# MCU.net
KiCad netlist of a schematic drawn in Altium Designer
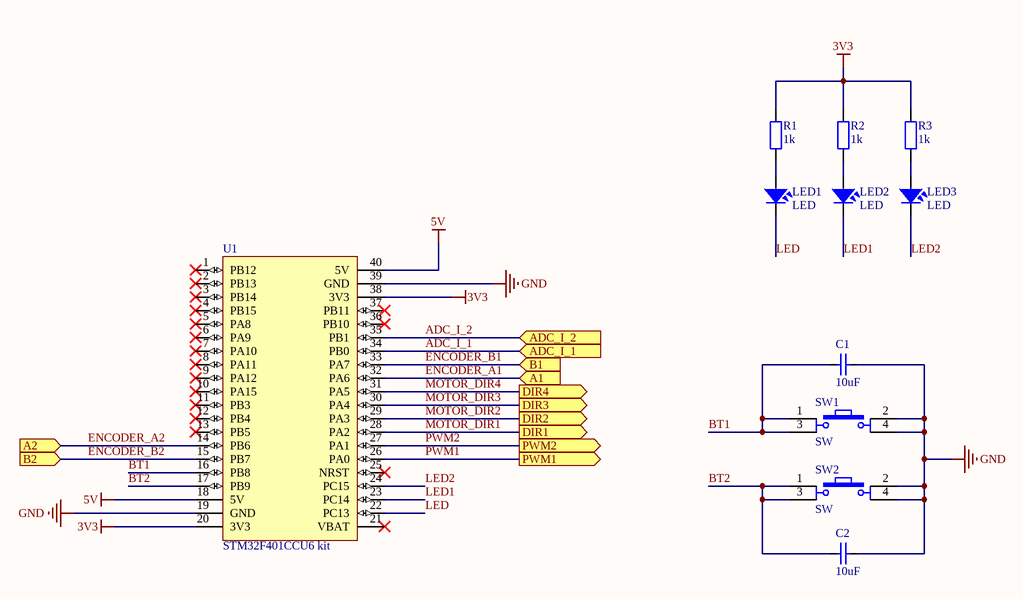
[diagram p0: MCU.SchDoc]

(export (version "E")
  (design (tool "Eeschema 10.0.6"))
  (components
    (comp (ref "C1")
      (value "10uF")
      (footprint "CAP_0805")
      (description "Capacitor")
      (fields (field (name "PUBLISHER") "Altium Limited"))
      (libsource (lib "My Library") (part "CapSMD"))
    )
    (comp (ref "C2")
      (value "10uF")
      (footprint "CAP_0805")
      (description "Capacitor")
      (fields (field (name "PUBLISHER") "Altium Limited"))
      (libsource (lib "My Library") (part "CapSMD"))
    )
    (comp (ref "LED1")
      (value "LED")
      (footprint "LED-0805-Red")
      (description "LED Single colour Green and Red")
      (libsource (lib "My Library") (part "LED"))
    )
    (comp (ref "LED2")
      (value "LED")
      (footprint "LED-0805-Orange")
      (description "LED Single colour Green and Red")
      (libsource (lib "My Library") (part "LED"))
    )
    (comp (ref "LED3")
      (value "LED")
      (footprint "LED-0805-Green")
      (description "LED Single colour Green and Red")
      (libsource (lib "My Library") (part "LED"))
    )
    (comp (ref "R1")
      (value "1k")
      (footprint "RES-SMD-0805")
      (description "Resistor SMD")
      (fields
        (field (name "MANUFACTURER") "Generic Components")
        (field (name "PUBLISHER") "Altium Hobart Technology Centre")
      )
      (libsource (lib "My Library") (part "Resistor - SMD"))
    )
    (comp (ref "R2")
      (value "1k")
      (footprint "RES-SMD-0805")
      (description "Resistor SMD")
      (fields
        (field (name "MANUFACTURER") "Generic Components")
        (field (name "PUBLISHER") "Altium Hobart Technology Centre")
      )
      (libsource (lib "My Library") (part "Resistor - SMD"))
    )
    (comp (ref "R3")
      (value "1k")
      (footprint "RES-SMD-0805")
      (description "Resistor SMD")
      (fields
        (field (name "MANUFACTURER") "Generic Components")
        (field (name "PUBLISHER") "Altium Hobart Technology Centre")
      )
      (libsource (lib "My Library") (part "Resistor - SMD"))
    )
    (comp (ref "SW1")
      (value "SW")
      (footprint "SW4")
      (description "Switch button 4 pin")
      (libsource (lib "My Library") (part "SW4"))
    )
    (comp (ref "SW2")
      (value "SW")
      (footprint "SW4")
      (description "Switch button 4 pin")
      (libsource (lib "My Library") (part "SW4"))
    )
    (comp (ref "U1")
      (value "STM32F401CCU6 kit")
      (footprint "STM32F401 KIT")
      (description "STM32F401CCU6 breakout board. STM32 ARM-based 32-bit MCU")
      (libsource (lib "My Library") (part "STM32F401CCU6"))
    )
  )
  (nets
    (net (code "1") (name "/ADC_I_1") (class "Default")
      (node (ref "U1") (pin "34") (pinfunction "PB0_34") (pintype "bidirectional"))
    )
    (net (code "2") (name "/ADC_I_2") (class "Default")
      (node (ref "U1") (pin "35") (pinfunction "PB1_35") (pintype "bidirectional"))
    )
    (net (code "3") (name "/BT1") (class "Default")
      (node (ref "C1") (pin "1") (pinfunction "1_1") (pintype "passive"))
      (node (ref "SW1") (pin "1") (pintype "passive"))
      (node (ref "SW1") (pin "3") (pintype "passive"))
      (node (ref "U1") (pin "16") (pinfunction "PB8_16") (pintype "bidirectional"))
    )
    (net (code "4") (name "/BT2") (class "Default")
      (node (ref "C2") (pin "1") (pinfunction "1_1") (pintype "passive"))
      (node (ref "SW2") (pin "1") (pintype "passive"))
      (node (ref "SW2") (pin "3") (pintype "passive"))
      (node (ref "U1") (pin "17") (pinfunction "PB9_17") (pintype "bidirectional"))
    )
    (net (code "5") (name "/ENCODER_A1") (class "Default")
      (node (ref "U1") (pin "32") (pinfunction "PA6_32") (pintype "bidirectional"))
    )
    (net (code "6") (name "/ENCODER_A2") (class "Default")
      (node (ref "U1") (pin "14") (pinfunction "PB6_14") (pintype "bidirectional"))
    )
    (net (code "7") (name "/ENCODER_B1") (class "Default")
      (node (ref "U1") (pin "33") (pinfunction "PA7_33") (pintype "bidirectional"))
    )
    (net (code "8") (name "/ENCODER_B2") (class "Default")
      (node (ref "U1") (pin "15") (pinfunction "PB7_15") (pintype "bidirectional"))
    )
    (net (code "9") (name "/LED") (class "Default")
      (node (ref "LED1") (pin "2") (pinfunction "2_2") (pintype "passive"))
      (node (ref "U1") (pin "22") (pinfunction "PC13_22") (pintype "bidirectional"))
    )
    (net (code "10") (name "/LED1") (class "Default")
      (node (ref "LED2") (pin "2") (pinfunction "2_2") (pintype "passive"))
      (node (ref "U1") (pin "23") (pinfunction "PC14_23") (pintype "bidirectional"))
    )
    (net (code "11") (name "/LED2") (class "Default")
      (node (ref "LED3") (pin "2") (pinfunction "2_2") (pintype "passive"))
      (node (ref "U1") (pin "24") (pinfunction "PC15_24") (pintype "bidirectional"))
    )
    (net (code "12") (name "/MOTOR_DIR1") (class "Default")
      (node (ref "U1") (pin "28") (pinfunction "PA2_28") (pintype "bidirectional"))
    )
    (net (code "13") (name "/MOTOR_DIR2") (class "Default")
      (node (ref "U1") (pin "29") (pinfunction "PA3_29") (pintype "bidirectional"))
    )
    (net (code "14") (name "/MOTOR_DIR3") (class "Default")
      (node (ref "U1") (pin "30") (pinfunction "PA4_30") (pintype "bidirectional"))
    )
    (net (code "15") (name "/MOTOR_DIR4") (class "Default")
      (node (ref "U1") (pin "31") (pinfunction "PA5_31") (pintype "bidirectional"))
    )
    (net (code "16") (name "/PWM1") (class "Default")
      (node (ref "U1") (pin "26") (pinfunction "PA0_26") (pintype "bidirectional"))
    )
    (net (code "17") (name "/PWM2") (class "Default")
      (node (ref "U1") (pin "27") (pinfunction "PA1_27") (pintype "bidirectional"))
    )
    (net (code "18") (name "3V3") (class "Default")
      (node (ref "R1") (pin "1") (pinfunction "1_1") (pintype "passive"))
      (node (ref "R2") (pin "1") (pinfunction "1_1") (pintype "passive"))
      (node (ref "R3") (pin "1") (pinfunction "1_1") (pintype "passive"))
      (node (ref "U1") (pin "20") (pinfunction "3V3_20") (pintype "power_in"))
      (node (ref "U1") (pin "38") (pinfunction "3V3_38") (pintype "power_in"))
    )
    (net (code "19") (name "5V") (class "Default")
      (node (ref "U1") (pin "18") (pinfunction "5V_18") (pintype "power_in"))
      (node (ref "U1") (pin "40") (pinfunction "5V_40") (pintype "power_in"))
    )
    (net (code "20") (name "GND") (class "Default")
      (node (ref "C1") (pin "2") (pinfunction "2_2") (pintype "passive"))
      (node (ref "C2") (pin "2") (pinfunction "2_2") (pintype "passive"))
      (node (ref "SW1") (pin "2") (pintype "passive"))
      (node (ref "SW1") (pin "4") (pintype "passive"))
      (node (ref "SW2") (pin "2") (pintype "passive"))
      (node (ref "SW2") (pin "4") (pintype "passive"))
      (node (ref "U1") (pin "19") (pinfunction "GND_19") (pintype "power_in"))
      (node (ref "U1") (pin "39") (pinfunction "GND_39") (pintype "power_in"))
    )
    (net (code "21") (name "Net-(LED1-Pad1)") (class "Default")
      (node (ref "LED1") (pin "1") (pinfunction "1_1") (pintype "passive"))
      (node (ref "R1") (pin "2") (pinfunction "2_2") (pintype "passive"))
    )
    (net (code "22") (name "Net-(LED2-Pad1)") (class "Default")
      (node (ref "LED2") (pin "1") (pinfunction "1_1") (pintype "passive"))
      (node (ref "R2") (pin "2") (pinfunction "2_2") (pintype "passive"))
    )
    (net (code "23") (name "Net-(LED3-Pad1)") (class "Default")
      (node (ref "LED3") (pin "1") (pinfunction "1_1") (pintype "passive"))
      (node (ref "R3") (pin "2") (pinfunction "2_2") (pintype "passive"))
    )
    (net (code "24") (name "unconnected-(U1-NRST-Pad25)") (class "Default")
      (node (ref "U1") (pin "25") (pinfunction "NRST_25") (pintype "bidirectional+no_connect"))
    )
    (net (code "25") (name "unconnected-(U1-PA8-Pad5)") (class "Default")
      (node (ref "U1") (pin "5") (pinfunction "PA8_5") (pintype "bidirectional+no_connect"))
    )
    (net (code "26") (name "unconnected-(U1-PA9-Pad6)") (class "Default")
      (node (ref "U1") (pin "6") (pinfunction "PA9_6") (pintype "bidirectional+no_connect"))
    )
    (net (code "27") (name "unconnected-(U1-PA10-Pad7)") (class "Default")
      (node (ref "U1") (pin "7") (pinfunction "PA10_7") (pintype "bidirectional+no_connect"))
    )
    (net (code "28") (name "unconnected-(U1-PA11-Pad8)") (class "Default")
      (node (ref "U1") (pin "8") (pinfunction "PA11_8") (pintype "bidirectional+no_connect"))
    )
    (net (code "29") (name "unconnected-(U1-PA12-Pad9)") (class "Default")
      (node (ref "U1") (pin "9") (pinfunction "PA12_9") (pintype "bidirectional+no_connect"))
    )
    (net (code "30") (name "unconnected-(U1-PA15-Pad10)") (class "Default")
      (node (ref "U1") (pin "10") (pinfunction "PA15_10") (pintype "bidirectional+no_connect"))
    )
    (net (code "31") (name "unconnected-(U1-PB3-Pad11)") (class "Default")
      (node (ref "U1") (pin "11") (pinfunction "PB3_11") (pintype "bidirectional+no_connect"))
    )
    (net (code "32") (name "unconnected-(U1-PB4-Pad12)") (class "Default")
      (node (ref "U1") (pin "12") (pinfunction "PB4_12") (pintype "bidirectional+no_connect"))
    )
    (net (code "33") (name "unconnected-(U1-PB5-Pad13)") (class "Default")
      (node (ref "U1") (pin "13") (pinfunction "PB5_13") (pintype "bidirectional+no_connect"))
    )
    (net (code "34") (name "unconnected-(U1-PB10-Pad36)") (class "Default")
      (node (ref "U1") (pin "36") (pinfunction "PB10_36") (pintype "bidirectional+no_connect"))
    )
    (net (code "35") (name "unconnected-(U1-PB11-Pad37)") (class "Default")
      (node (ref "U1") (pin "37") (pinfunction "PB11_37") (pintype "bidirectional+no_connect"))
    )
    (net (code "36") (name "unconnected-(U1-PB12-Pad1)") (class "Default")
      (node (ref "U1") (pin "1") (pinfunction "PB12_1") (pintype "bidirectional+no_connect"))
    )
    (net (code "37") (name "unconnected-(U1-PB13-Pad2)") (class "Default")
      (node (ref "U1") (pin "2") (pinfunction "PB13_2") (pintype "bidirectional+no_connect"))
    )
    (net (code "38") (name "unconnected-(U1-PB14-Pad3)") (class "Default")
      (node (ref "U1") (pin "3") (pinfunction "PB14_3") (pintype "bidirectional+no_connect"))
    )
    (net (code "39") (name "unconnected-(U1-PB15-Pad4)") (class "Default")
      (node (ref "U1") (pin "4") (pinfunction "PB15_4") (pintype "bidirectional+no_connect"))
    )
    (net (code "40") (name "unconnected-(U1-VBAT-Pad21)") (class "Default")
      (node (ref "U1") (pin "21") (pinfunction "VBAT_21") (pintype "power_in+no_connect"))
    )
  )
)
